# miniUPS.net
KiCad netlist of a schematic drawn in EAGLE
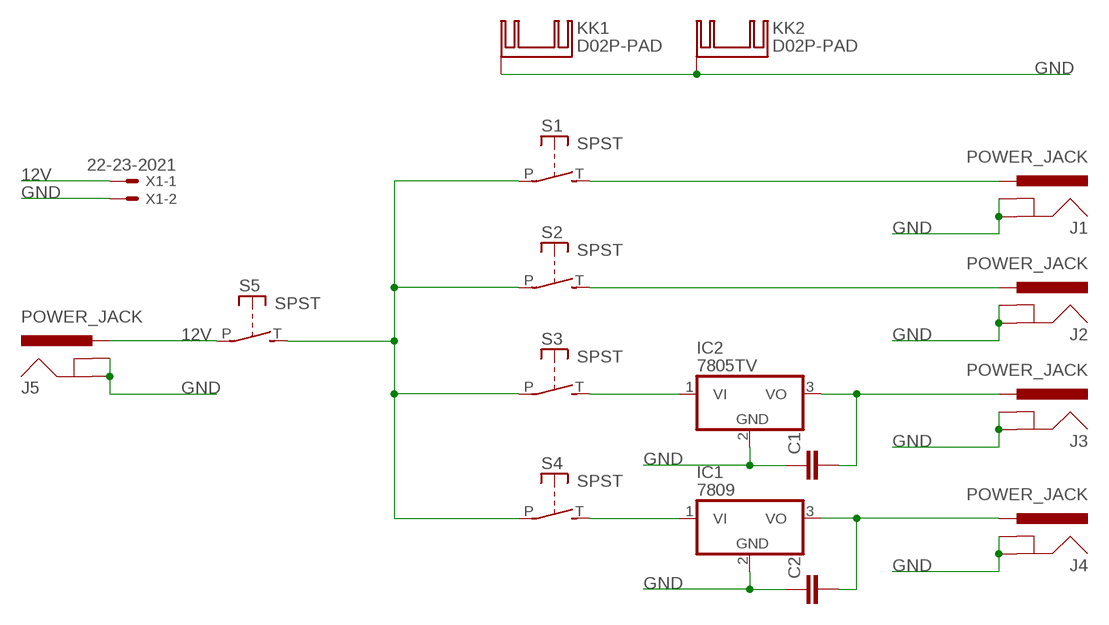
[diagram p0: schematic, sheet 1]

(export (version "E")
  (design (tool "Eeschema 10.0.6"))
  (components
    (comp (ref "C1")
      (value "CAPPTH2")
      (footprint "eagle-import:CAP-PTH-SMALL2")
      (libsource (lib "eagle-import") (part "CAPPTH2"))
    )
    (comp (ref "C2")
      (value "CAPPTH2")
      (footprint "eagle-import:CAP-PTH-SMALL2")
      (libsource (lib "eagle-import") (part "CAPPTH2"))
    )
    (comp (ref "IC1")
      (value "7809")
      (footprint "eagle-import:TO220V")
      (libsource (lib "eagle-import") (part "78TV05"))
    )
    (comp (ref "IC2")
      (value "7805TV")
      (footprint "eagle-import:TO220V")
      (libsource (lib "eagle-import") (part "78TV05"))
    )
    (comp (ref "J1")
      (value "POWER_JACK")
      (footprint "eagle-import:POWER_JACK_PTH")
      (libsource (lib "eagle-import") (part "POWER_JACK"))
    )
    (comp (ref "J2")
      (value "POWER_JACK")
      (footprint "eagle-import:POWER_JACK_PTH")
      (libsource (lib "eagle-import") (part "POWER_JACK"))
    )
    (comp (ref "J3")
      (value "POWER_JACK")
      (footprint "eagle-import:POWER_JACK_PTH")
      (libsource (lib "eagle-import") (part "POWER_JACK"))
    )
    (comp (ref "J4")
      (value "POWER_JACK")
      (footprint "eagle-import:POWER_JACK_PTH")
      (libsource (lib "eagle-import") (part "POWER_JACK"))
    )
    (comp (ref "J5")
      (value "POWER_JACK")
      (footprint "eagle-import:POWER_JACK_PTH")
      (libsource (lib "eagle-import") (part "POWER_JACK"))
    )
    (comp (ref "KK1")
      (value "D02P-PAD")
      (footprint "eagle-import:D02PA-PAD")
      (libsource (lib "eagle-import") (part "D02P-PAD"))
    )
    (comp (ref "KK2")
      (value "D02P-PAD")
      (footprint "eagle-import:D02PA-PAD")
      (libsource (lib "eagle-import") (part "D02P-PAD"))
    )
    (comp (ref "S1")
      (value "SPST")
      (footprint "eagle-import:JUDCOSPST")
      (libsource (lib "eagle-import") (part "SPST"))
    )
    (comp (ref "S2")
      (value "SPST")
      (footprint "eagle-import:JUDCOSPST")
      (libsource (lib "eagle-import") (part "SPST"))
    )
    (comp (ref "S3")
      (value "SPST")
      (footprint "eagle-import:JUDCOSPST")
      (libsource (lib "eagle-import") (part "SPST"))
    )
    (comp (ref "S4")
      (value "SPST")
      (footprint "eagle-import:JUDCOSPST")
      (libsource (lib "eagle-import") (part "SPST"))
    )
    (comp (ref "S5")
      (value "SPST")
      (footprint "eagle-import:JUDCOSPST")
      (libsource (lib "eagle-import") (part "SPST"))
    )
    (comp (ref "X1")
      (value "22-23-2021")
      (footprint "eagle-import:22-23-2021")
      (fields (field (name "MF") "MOLEX"))
      (libsource (lib "eagle-import") (part "22-23-2021"))
    )
  )
  (nets
    (net (code "1") (name "/12V") (class "Default")
      (node (ref "J5") (pin "PWR") (pinfunction "PWR_PWR") (pintype "bidirectional"))
      (node (ref "S5") (pin "P") (pinfunction "P_P") (pintype "passive"))
      (node (ref "X1") (pin "1") (pinfunction "S_1") (pintype "passive"))
    )
    (net (code "2") (name "/GND") (class "Default")
      (node (ref "C1") (pin "1") (pinfunction "1_1") (pintype "passive"))
      (node (ref "C2") (pin "1") (pinfunction "1_1") (pintype "passive"))
      (node (ref "IC1") (pin "2") (pinfunction "GND_2") (pintype "passive"))
      (node (ref "IC2") (pin "2") (pinfunction "GND_2") (pintype "passive"))
      (node (ref "J1") (pin "GND") (pinfunction "GND_GND") (pintype "bidirectional"))
      (node (ref "J1") (pin "GNDBREAK") (pinfunction "GNDBREAK_GNDBREAK") (pintype "bidirectional"))
      (node (ref "J2") (pin "GND") (pinfunction "GND_GND") (pintype "bidirectional"))
      (node (ref "J2") (pin "GNDBREAK") (pinfunction "GNDBREAK_GNDBREAK") (pintype "bidirectional"))
      (node (ref "J3") (pin "GND") (pinfunction "GND_GND") (pintype "bidirectional"))
      (node (ref "J3") (pin "GNDBREAK") (pinfunction "GNDBREAK_GNDBREAK") (pintype "bidirectional"))
      (node (ref "J4") (pin "GND") (pinfunction "GND_GND") (pintype "bidirectional"))
      (node (ref "J4") (pin "GNDBREAK") (pinfunction "GNDBREAK_GNDBREAK") (pintype "bidirectional"))
      (node (ref "J5") (pin "GND") (pinfunction "GND_GND") (pintype "bidirectional"))
      (node (ref "J5") (pin "GNDBREAK") (pinfunction "GNDBREAK_GNDBREAK") (pintype "bidirectional"))
      (node (ref "KK1") (pin "B") (pinfunction "K_B") (pintype "passive"))
      (node (ref "KK2") (pin "B") (pinfunction "K_B") (pintype "passive"))
      (node (ref "X1") (pin "2") (pinfunction "S_2") (pintype "passive"))
    )
    (net (code "3") (name "Net-(IC1-VI)") (class "Default")
      (node (ref "IC1") (pin "1") (pinfunction "VI_1") (pintype "input"))
      (node (ref "S4") (pin "T") (pinfunction "S_T") (pintype "passive"))
    )
    (net (code "4") (name "Net-(IC1-VO)") (class "Default")
      (node (ref "C2") (pin "2") (pinfunction "2_2") (pintype "passive"))
      (node (ref "IC1") (pin "3") (pinfunction "VO_3") (pintype "passive"))
      (node (ref "J4") (pin "PWR") (pinfunction "PWR_PWR") (pintype "bidirectional"))
    )
    (net (code "5") (name "Net-(IC2-VI)") (class "Default")
      (node (ref "IC2") (pin "1") (pinfunction "VI_1") (pintype "input"))
      (node (ref "S3") (pin "T") (pinfunction "S_T") (pintype "passive"))
    )
    (net (code "6") (name "Net-(IC2-VO)") (class "Default")
      (node (ref "C1") (pin "2") (pinfunction "2_2") (pintype "passive"))
      (node (ref "IC2") (pin "3") (pinfunction "VO_3") (pintype "passive"))
      (node (ref "J3") (pin "PWR") (pinfunction "PWR_PWR") (pintype "bidirectional"))
    )
    (net (code "7") (name "Net-(S1-S)") (class "Default")
      (node (ref "J1") (pin "PWR") (pinfunction "PWR_PWR") (pintype "bidirectional"))
      (node (ref "S1") (pin "T") (pinfunction "S_T") (pintype "passive"))
    )
    (net (code "8") (name "Net-(S2-S)") (class "Default")
      (node (ref "J2") (pin "PWR") (pinfunction "PWR_PWR") (pintype "bidirectional"))
      (node (ref "S2") (pin "T") (pinfunction "S_T") (pintype "passive"))
    )
    (net (code "9") (name "Net-(S5-S)") (class "Default")
      (node (ref "S1") (pin "P") (pinfunction "P_P") (pintype "passive"))
      (node (ref "S2") (pin "P") (pinfunction "P_P") (pintype "passive"))
      (node (ref "S3") (pin "P") (pinfunction "P_P") (pintype "passive"))
      (node (ref "S4") (pin "P") (pinfunction "P_P") (pintype "passive"))
      (node (ref "S5") (pin "T") (pinfunction "S_T") (pintype "passive"))
    )
  )
)
